# 12-5-3_3_card_concept__panther.net
KiCad netlist of a schematic drawn in EasyEDA Pro
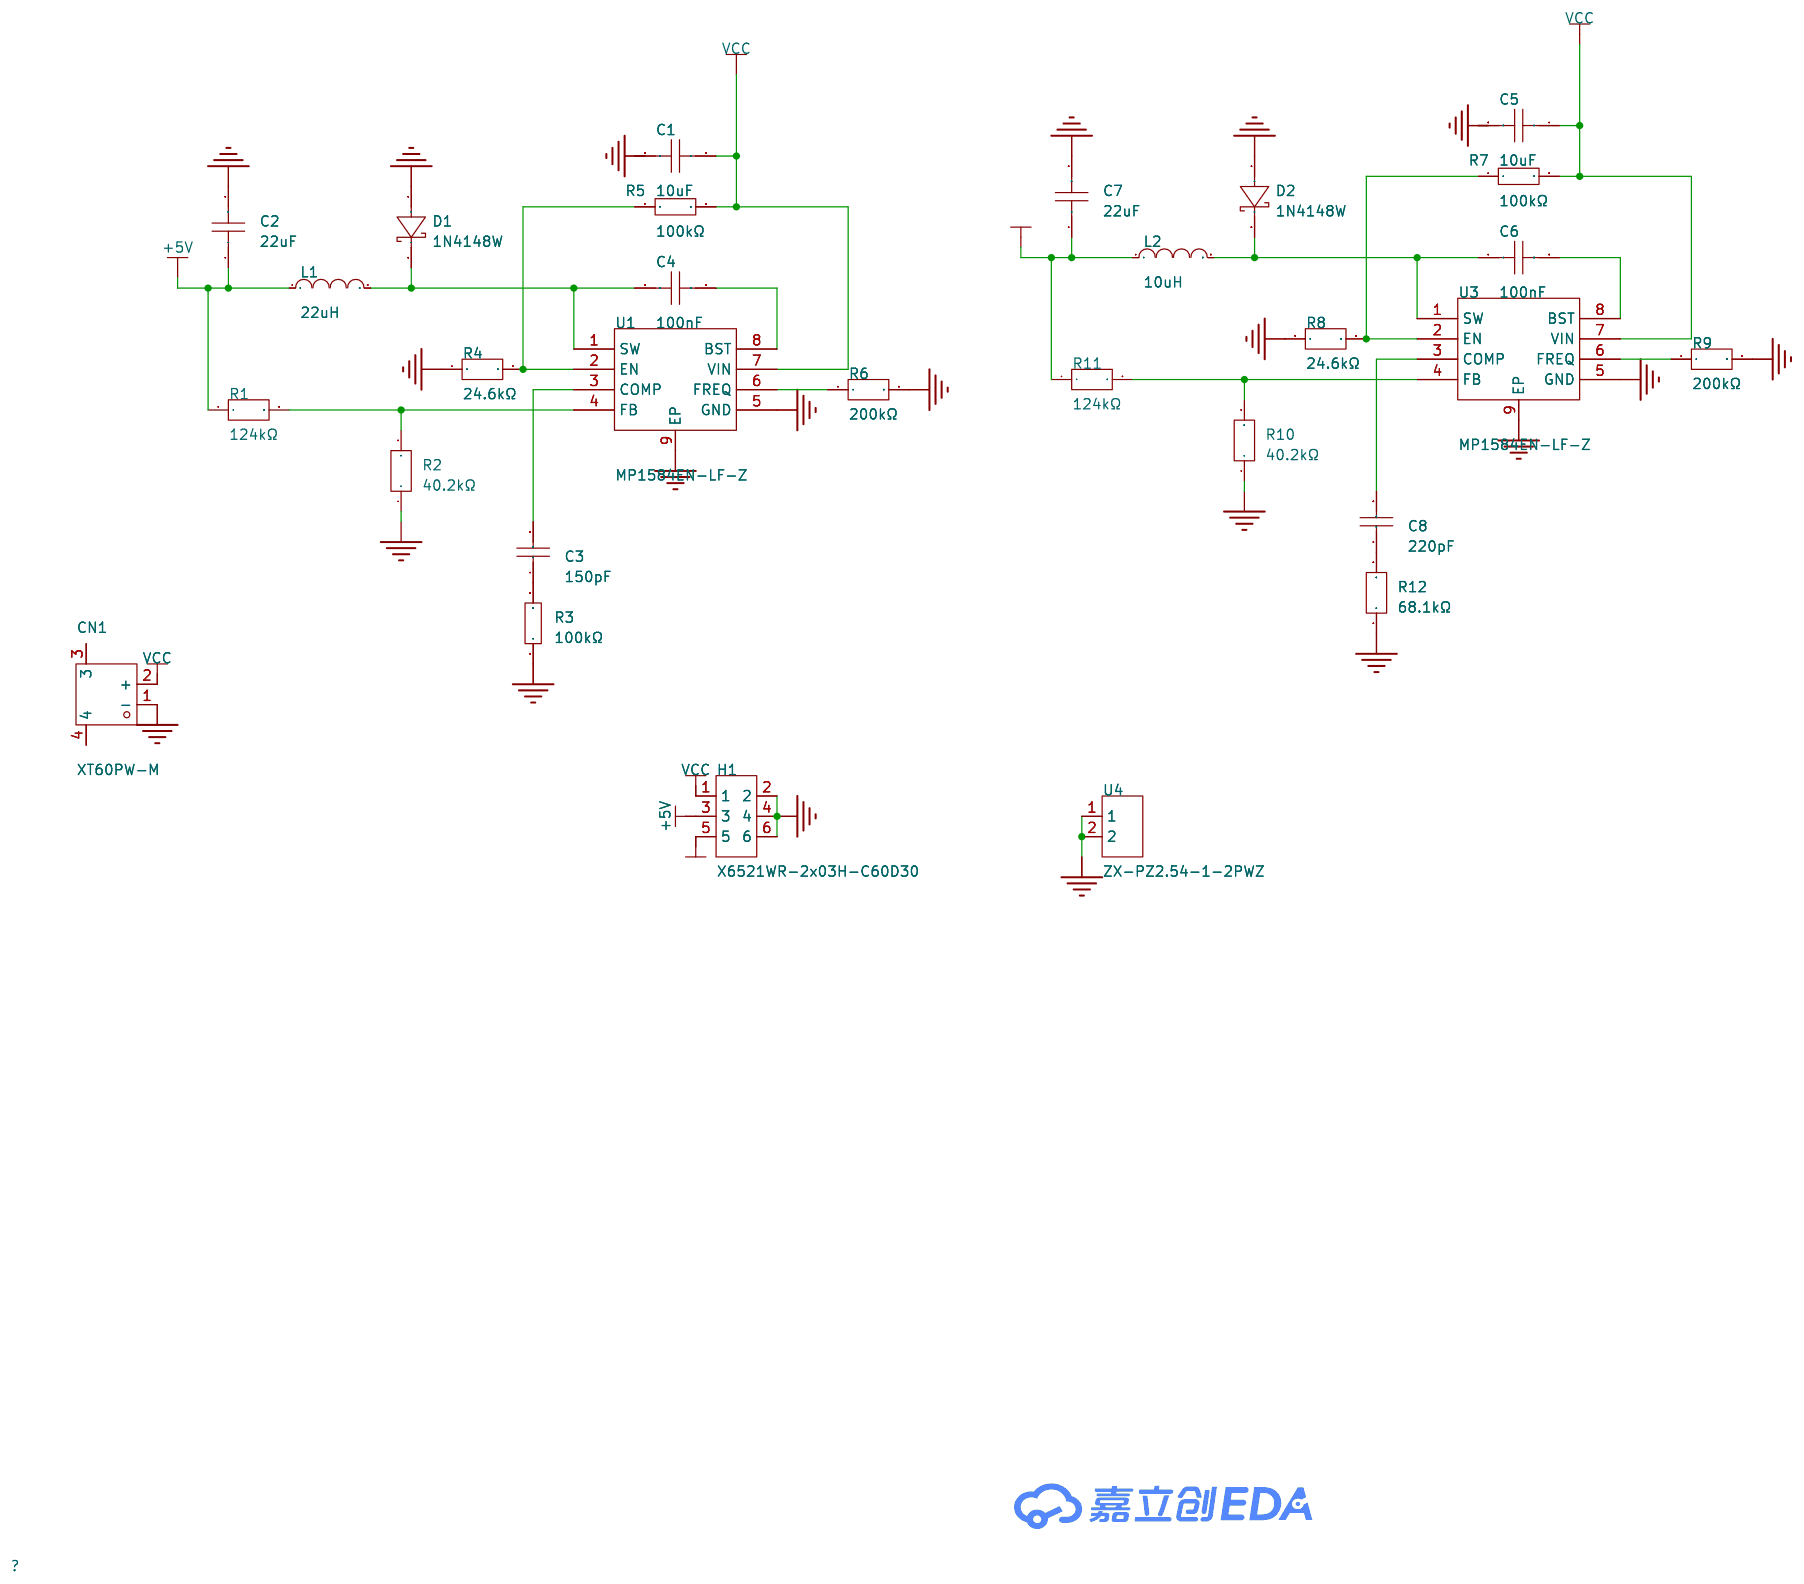
[diagram p0: schematic sheet]

(export (version "E")
  (design (tool "Eeschema 10.0.6"))
  (components
    (comp (ref "C1")
      (value "10uF")
      (footprint "easyedapro:C1206")
      (description "容值:10uF;精度:±10%;额定电压:50V;温度系数:X5R;")
      (fields
        (field (name "Manufacturer Part") "HGC1206R5106K500NSPJ")
        (field (name "Manufacturer") "Chinocera(华瓷)")
      )
      (libsource (lib "easyedapro") (part "HGC1206R5106K500NSPJ"))
    )
    (comp (ref "C2")
      (value "22uF")
      (footprint "easyedapro:C0805")
      (description "容值:22uF;精度:±20%;额定电压:35V;材质(温度系数):X5R;")
      (fields
        (field (name "Manufacturer Part") "CGA0805X5R226M350MT")
        (field (name "Manufacturer") "HRE(芯声)")
      )
      (libsource (lib "easyedapro") (part "CGA0805X5R226M350MT"))
    )
    (comp (ref "C3")
      (value "150pF")
      (footprint "easyedapro:C0603")
      (description "容值:150pF;精度:±10%;额定电压:50V;温度系数:X7R;")
      (fields (field (name "Manufacturer Part") "0603B151K500NT") (field (name "Manufacturer") "FH(风华)"))
      (libsource (lib "easyedapro") (part "0603B151K500NT"))
    )
    (comp (ref "C4")
      (value "100nF")
      (footprint "easyedapro:C0603")
      (description "容值:100nF;精度:±10%;额定电压:50V;材质(温度系数):X7R;")
      (fields
        (field (name "Manufacturer Part") "CGA0603X7R104K500JT")
        (field (name "Manufacturer") "HRE(芯声)")
      )
      (libsource (lib "easyedapro") (part "CGA0603X7R104K500JT"))
    )
    (comp (ref "C5")
      (value "10uF")
      (footprint "easyedapro:C1206")
      (description "容值:10uF;精度:±10%;额定电压:50V;温度系数:X5R;")
      (fields
        (field (name "Manufacturer Part") "HGC1206R5106K500NSPJ")
        (field (name "Manufacturer") "Chinocera(华瓷)")
      )
      (libsource (lib "easyedapro") (part "HGC1206R5106K500NSPJ"))
    )
    (comp (ref "C6")
      (value "100nF")
      (footprint "easyedapro:C0603")
      (description "容值:100nF;精度:±10%;额定电压:50V;材质(温度系数):X7R;")
      (fields
        (field (name "Manufacturer Part") "CGA0603X7R104K500JT")
        (field (name "Manufacturer") "HRE(芯声)")
      )
      (libsource (lib "easyedapro") (part "CGA0603X7R104K500JT"))
    )
    (comp (ref "C7")
      (value "22uF")
      (footprint "easyedapro:C0805")
      (description "容值:22uF;精度:±20%;额定电压:35V;材质(温度系数):X5R;")
      (fields
        (field (name "Manufacturer Part") "CGA0805X5R226M350MT")
        (field (name "Manufacturer") "HRE(芯声)")
      )
      (libsource (lib "easyedapro") (part "CGA0805X5R226M350MT"))
    )
    (comp (ref "C8")
      (value "220pF")
      (footprint "easyedapro:C0603")
      (description "容值:220pF;精度:±10%;额定电压:50V;材质(温度系数):X7R;")
      (fields
        (field (name "Manufacturer Part") "CL10B221KB8NNNC")
        (field (name "Manufacturer") "SAMSUNG(三星)")
      )
      (libsource (lib "easyedapro") (part "CL10B221KB8NNNC"))
    )
    (comp (ref "CN1")
      (value "XT60PW-M")
      (footprint "easyedapro:CONN-TH_XT60PW-M")
      (description "类别:-;类型1:-;")
      (fields (field (name "Manufacturer") "AMASS(艾迈斯)"))
      (libsource (lib "easyedapro") (part "XT60PW-M"))
    )
    (comp (ref "D1")
      (value "1N4148W")
      (footprint "easyedapro:SOD-123_L2.7-W1.6-LS3.7-FD")
      (description "二极管配置:独立式;正向压降(Vf):1.25V@150mA;直流反向耐压(Vr):100V;整流电流:150mA;反向恢复时间(trr):4ns;")
      (fields (field (name "Manufacturer") "宏迦橙"))
      (libsource (lib "easyedapro") (part "1N4148W_C7420318"))
    )
    (comp (ref "D2")
      (value "1N4148W")
      (footprint "easyedapro:SOD-123_L2.7-W1.6-LS3.7-FD")
      (description "二极管配置:独立式;正向压降(Vf):1.25V@150mA;直流反向耐压(Vr):100V;整流电流:150mA;反向恢复时间(trr):4ns;")
      (fields (field (name "Manufacturer") "宏迦橙"))
      (libsource (lib "easyedapro") (part "1N4148W_C7420318"))
    )
    (comp (ref "H1")
      (value "X6521WR-2x03H-C60D30")
      (footprint "easyedapro:HDR-TH_6P-P2.54-H-M-R2-C3-S2.54-W12.3-N")
      (fields (field (name "Manufacturer") "XKB Connection(中国星坤)"))
      (libsource (lib "easyedapro") (part "X6521WR-2×03H-C30D60"))
    )
    (comp (ref "L1")
      (value "22uH")
      (footprint "easyedapro:IND-SMD_L7.0-W6.6_FXL0630")
      (description "电感值:22uH;精度:±20%;额定电流:2.5A;饱和电流(Isat):3A;类型:一体成型电感;")
      (fields (field (name "Manufacturer Part") "FXL0630-220-M") (field (name "Manufacturer") "cjiang(长江微电)"))
      (libsource (lib "easyedapro") (part "FXL0630-220-M"))
    )
    (comp (ref "L2")
      (value "10uH")
      (footprint "easyedapro:IND-SMD_L7.3-W6.8")
      (description "电感值:10uH;精度:±20%;额定电流:4.5A;饱和电流(Isat):5.5A;类型:一体成型电感;")
      (fields (field (name "Manufacturer Part") "FXL0630-100-M") (field (name "Manufacturer") "cjiang(长江微电)"))
      (libsource (lib "easyedapro") (part "FXL0630-100-M"))
    )
    (comp (ref "R1")
      (value "124kΩ")
      (footprint "easyedapro:R0603")
      (description "电阻类型:厚膜电阻;阻值:124kΩ;精度:±1%;功率:100mW;最大工作电压:75V;温度系数:±100ppm/°C;")
      (fields (field (name "Manufacturer Part") "FRC0603F1243TS") (field (name "Manufacturer") "FOJAN(富捷)"))
      (libsource (lib "easyedapro") (part "FRC0603F1243TS"))
    )
    (comp (ref "R2")
      (value "40.2kΩ")
      (footprint "easyedapro:R0603")
      (description "电阻类型:厚膜电阻;阻值:40.2kΩ;精度:±1%;功率:100mW;最大工作电压:75V;温度系数:±100ppm/°C;")
      (fields (field (name "Manufacturer Part") "FRC0603F4022TS") (field (name "Manufacturer") "FOJAN(富捷)"))
      (libsource (lib "easyedapro") (part "FRC0603F4022TS"))
    )
    (comp (ref "R3")
      (value "100kΩ")
      (footprint "easyedapro:R0603")
      (description "电阻类型:厚膜电阻;阻值:100kΩ;精度:±1%;功率:100mW;最大工作电压:75V;温度系数:±100ppm/°C;")
      (fields
        (field (name "Manufacturer Part") "0603WAF1003T5E")
        (field (name "Manufacturer") "UNI-ROYAL(厚声)")
      )
      (libsource (lib "easyedapro") (part "0603WAF1003T5E"))
    )
    (comp (ref "R4")
      (value "24.6kΩ")
      (footprint "easyedapro:R0603")
      (description "电阻类型:薄膜电阻;阻值:24.6kΩ;精度:±0.1%;功率:100mW;温度系数:±25ppm/°C;")
      (fields (field (name "Manufacturer Part") "RT0603BRD0724K6L") (field (name "Manufacturer") "YAGEO(国巨)"))
      (libsource (lib "easyedapro") (part "RT0603BRD0724K6L"))
    )
    (comp (ref "R5")
      (value "100kΩ")
      (footprint "easyedapro:R0603")
      (description "电阻类型:厚膜电阻;阻值:100kΩ;精度:±1%;功率:100mW;最大工作电压:75V;温度系数:±100ppm/°C;")
      (fields
        (field (name "Manufacturer Part") "0603WAF1003T5E")
        (field (name "Manufacturer") "UNI-ROYAL(厚声)")
      )
      (libsource (lib "easyedapro") (part "0603WAF1003T5E"))
    )
    (comp (ref "R6")
      (value "200kΩ")
      (footprint "easyedapro:R0603")
      (description "电阻类型:厚膜电阻;阻值:200kΩ;精度:±1%;功率:100mW;工作电压:75V;温度系数:±100ppm/°C;")
      (fields (field (name "Manufacturer Part") "FRC0603F2003TS") (field (name "Manufacturer") "FOJAN(富捷)"))
      (libsource (lib "easyedapro") (part "FRC0603F2003TS"))
    )
    (comp (ref "R7")
      (value "100kΩ")
      (footprint "easyedapro:R0603")
      (description "电阻类型:厚膜电阻;阻值:100kΩ;精度:±1%;功率:100mW;最大工作电压:75V;温度系数:±100ppm/°C;")
      (fields
        (field (name "Manufacturer Part") "0603WAF1003T5E")
        (field (name "Manufacturer") "UNI-ROYAL(厚声)")
      )
      (libsource (lib "easyedapro") (part "0603WAF1003T5E"))
    )
    (comp (ref "R8")
      (value "24.6kΩ")
      (footprint "easyedapro:R0603")
      (description "电阻类型:薄膜电阻;阻值:24.6kΩ;精度:±0.1%;功率:100mW;温度系数:±25ppm/°C;")
      (fields (field (name "Manufacturer Part") "RT0603BRD0724K6L") (field (name "Manufacturer") "YAGEO(国巨)"))
      (libsource (lib "easyedapro") (part "RT0603BRD0724K6L"))
    )
    (comp (ref "R9")
      (value "200kΩ")
      (footprint "easyedapro:R0603")
      (description "电阻类型:厚膜电阻;阻值:200kΩ;精度:±1%;功率:100mW;工作电压:75V;温度系数:±100ppm/°C;")
      (fields (field (name "Manufacturer Part") "FRC0603F2003TS") (field (name "Manufacturer") "FOJAN(富捷)"))
      (libsource (lib "easyedapro") (part "FRC0603F2003TS"))
    )
    (comp (ref "R10")
      (value "40.2kΩ")
      (footprint "easyedapro:R0603")
      (description "电阻类型:厚膜电阻;阻值:40.2kΩ;精度:±1%;功率:100mW;最大工作电压:75V;温度系数:±100ppm/°C;")
      (fields (field (name "Manufacturer Part") "FRC0603F4022TS") (field (name "Manufacturer") "FOJAN(富捷)"))
      (libsource (lib "easyedapro") (part "FRC0603F4022TS"))
    )
    (comp (ref "R11")
      (value "124kΩ")
      (footprint "easyedapro:R0603")
      (description "电阻类型:厚膜电阻;阻值:124kΩ;精度:±1%;功率:100mW;最大工作电压:75V;温度系数:±100ppm/°C;")
      (fields (field (name "Manufacturer Part") "FRC0603F1243TS") (field (name "Manufacturer") "FOJAN(富捷)"))
      (libsource (lib "easyedapro") (part "FRC0603F1243TS"))
    )
    (comp (ref "R12")
      (value "68.1kΩ")
      (footprint "easyedapro:R0603")
      (description "电阻类型:厚膜电阻;阻值:68.1kΩ;精度:±1%;功率:100mW;最大工作电压:75V;温度系数:±100ppm/°C;")
      (fields (field (name "Manufacturer Part") "FRC0603F6812TS") (field (name "Manufacturer") "FOJAN(富捷)"))
      (libsource (lib "easyedapro") (part "FRC0603F6812TS"))
    )
    (comp (ref "U1")
      (value "MP1584EN-LF-Z")
      (footprint "easyedapro:SOIC-8_L5.0-W4.0-P1.27-LS6.0-BL-EP2.0")
      (description "功能类型:降压型;输出类型:固定;工作电压:4.5V~28V;输出电压:800mV~25V;输出电流:3A;")
      (fields (field (name "Manufacturer") "MPS(芯源)"))
      (libsource (lib "easyedapro") (part "MP1584EN-LF-Z"))
    )
    (comp (ref "U3")
      (value "MP1584EN-LF-Z")
      (footprint "easyedapro:SOIC-8_L5.0-W4.0-P1.27-LS6.0-BL-EP2.0")
      (description "功能类型:降压型;输出类型:固定;工作电压:4.5V~28V;输出电压:800mV~25V;输出电流:3A;")
      (fields (field (name "Manufacturer") "MPS(芯源)"))
      (libsource (lib "easyedapro") (part "MP1584EN-LF-Z"))
    )
    (comp (ref "U4")
      (value "ZX-PZ2.54-1-2PWZ")
      (footprint "easyedapro:HDR-TH_2P-P2.54-H-M-W10.4")
      (fields (field (name "Manufacturer") "Megastar(兆星)"))
      (libsource (lib "easyedapro") (part "ZX-PZ2.54-1-2PWZ"))
    )
  )
  (nets
    (net (code "1") (name "+3.3V") (class "Default")
      (node (ref "C7") (pin "1") (pinfunction "1_1") (pintype "unspecified"))
      (node (ref "H1") (pin "5") (pinfunction "5_5") (pintype "unspecified"))
      (node (ref "L2") (pin "1") (pinfunction "1_1") (pintype "unspecified"))
      (node (ref "R11") (pin "1") (pinfunction "1_1") (pintype "unspecified"))
    )
    (net (code "2") (name "+5V") (class "Default")
      (node (ref "C2") (pin "1") (pinfunction "1_1") (pintype "unspecified"))
      (node (ref "H1") (pin "3") (pinfunction "3_3") (pintype "unspecified"))
      (node (ref "L1") (pin "1") (pinfunction "1_1") (pintype "unspecified"))
      (node (ref "R1") (pin "1") (pinfunction "1_1") (pintype "unspecified"))
    )
    (net (code "3") (name "GND") (class "Default")
      (node (ref "C1") (pin "2") (pinfunction "2_2") (pintype "unspecified"))
      (node (ref "C2") (pin "2") (pinfunction "2_2") (pintype "unspecified"))
      (node (ref "C5") (pin "2") (pinfunction "2_2") (pintype "unspecified"))
      (node (ref "C7") (pin "2") (pinfunction "2_2") (pintype "unspecified"))
      (node (ref "CN1") (pin "1") (pinfunction "-_1") (pintype "unspecified"))
      (node (ref "D1") (pin "1") (pinfunction "A_1") (pintype "unspecified"))
      (node (ref "D2") (pin "1") (pinfunction "A_1") (pintype "unspecified"))
      (node (ref "H1") (pin "2") (pinfunction "2_2") (pintype "unspecified"))
      (node (ref "H1") (pin "4") (pinfunction "4_4") (pintype "unspecified"))
      (node (ref "H1") (pin "6") (pinfunction "6_6") (pintype "unspecified"))
      (node (ref "R10") (pin "1") (pinfunction "1_1") (pintype "unspecified"))
      (node (ref "R12") (pin "1") (pinfunction "1_1") (pintype "unspecified"))
      (node (ref "R2") (pin "1") (pinfunction "1_1") (pintype "unspecified"))
      (node (ref "R3") (pin "1") (pinfunction "1_1") (pintype "input"))
      (node (ref "R4") (pin "1") (pinfunction "1_1") (pintype "unspecified"))
      (node (ref "R6") (pin "2") (pinfunction "2_2") (pintype "unspecified"))
      (node (ref "R8") (pin "1") (pinfunction "1_1") (pintype "unspecified"))
      (node (ref "R9") (pin "2") (pinfunction "2_2") (pintype "unspecified"))
      (node (ref "U1") (pin "5") (pinfunction "GND_5") (pintype "unspecified"))
      (node (ref "U1") (pin "9") (pinfunction "EP_9") (pintype "unspecified"))
      (node (ref "U3") (pin "5") (pinfunction "GND_5") (pintype "unspecified"))
      (node (ref "U3") (pin "9") (pinfunction "EP_9") (pintype "unspecified"))
      (node (ref "U4") (pin "1") (pinfunction "1_1") (pintype "unspecified"))
      (node (ref "U4") (pin "2") (pinfunction "2_2") (pintype "unspecified"))
    )
    (net (code "4") (name "Net-(C3-Pad1)") (class "Default")
      (node (ref "C3") (pin "1") (pinfunction "1_1") (pintype "input"))
      (node (ref "R3") (pin "2") (pinfunction "2_2") (pintype "input"))
    )
    (net (code "5") (name "Net-(C8-Pad1)") (class "Default")
      (node (ref "C8") (pin "1") (pinfunction "1_1") (pintype "input"))
      (node (ref "R12") (pin "2") (pinfunction "2_2") (pintype "unspecified"))
    )
    (net (code "6") (name "Net-(D1-K)") (class "Default")
      (node (ref "C4") (pin "1") (pinfunction "1_1") (pintype "unspecified"))
      (node (ref "D1") (pin "2") (pinfunction "K_2") (pintype "unspecified"))
      (node (ref "L1") (pin "2") (pinfunction "2_2") (pintype "unspecified"))
      (node (ref "U1") (pin "1") (pinfunction "SW_1") (pintype "unspecified"))
    )
    (net (code "7") (name "Net-(D2-K)") (class "Default")
      (node (ref "C6") (pin "1") (pinfunction "1_1") (pintype "unspecified"))
      (node (ref "D2") (pin "2") (pinfunction "K_2") (pintype "unspecified"))
      (node (ref "L2") (pin "2") (pinfunction "2_2") (pintype "unspecified"))
      (node (ref "U3") (pin "1") (pinfunction "SW_1") (pintype "unspecified"))
    )
    (net (code "8") (name "Net-(U1-BST)") (class "Default")
      (node (ref "C4") (pin "2") (pinfunction "2_2") (pintype "unspecified"))
      (node (ref "U1") (pin "8") (pinfunction "BST_8") (pintype "unspecified"))
    )
    (net (code "9") (name "Net-(U1-COMP)") (class "Default")
      (node (ref "C3") (pin "2") (pinfunction "2_2") (pintype "input"))
      (node (ref "U1") (pin "3") (pinfunction "COMP_3") (pintype "unspecified"))
    )
    (net (code "10") (name "Net-(U1-EN)") (class "Default")
      (node (ref "R4") (pin "2") (pinfunction "2_2") (pintype "unspecified"))
      (node (ref "R5") (pin "1") (pinfunction "1_1") (pintype "input"))
      (node (ref "U1") (pin "2") (pinfunction "EN_2") (pintype "unspecified"))
    )
    (net (code "11") (name "Net-(U1-FB)") (class "Default")
      (node (ref "R1") (pin "2") (pinfunction "2_2") (pintype "unspecified"))
      (node (ref "R2") (pin "2") (pinfunction "2_2") (pintype "unspecified"))
      (node (ref "U1") (pin "4") (pinfunction "FB_4") (pintype "unspecified"))
    )
    (net (code "12") (name "Net-(U1-FREQ)") (class "Default")
      (node (ref "R6") (pin "1") (pinfunction "1_1") (pintype "unspecified"))
      (node (ref "U1") (pin "6") (pinfunction "FREQ_6") (pintype "unspecified"))
    )
    (net (code "13") (name "Net-(U3-BST)") (class "Default")
      (node (ref "C6") (pin "2") (pinfunction "2_2") (pintype "unspecified"))
      (node (ref "U3") (pin "8") (pinfunction "BST_8") (pintype "unspecified"))
    )
    (net (code "14") (name "Net-(U3-COMP)") (class "Default")
      (node (ref "C8") (pin "2") (pinfunction "2_2") (pintype "input"))
      (node (ref "U3") (pin "3") (pinfunction "COMP_3") (pintype "unspecified"))
    )
    (net (code "15") (name "Net-(U3-EN)") (class "Default")
      (node (ref "R7") (pin "1") (pinfunction "1_1") (pintype "input"))
      (node (ref "R8") (pin "2") (pinfunction "2_2") (pintype "unspecified"))
      (node (ref "U3") (pin "2") (pinfunction "EN_2") (pintype "unspecified"))
    )
    (net (code "16") (name "Net-(U3-FB)") (class "Default")
      (node (ref "R10") (pin "2") (pinfunction "2_2") (pintype "unspecified"))
      (node (ref "R11") (pin "2") (pinfunction "2_2") (pintype "unspecified"))
      (node (ref "U3") (pin "4") (pinfunction "FB_4") (pintype "unspecified"))
    )
    (net (code "17") (name "Net-(U3-FREQ)") (class "Default")
      (node (ref "R9") (pin "1") (pinfunction "1_1") (pintype "unspecified"))
      (node (ref "U3") (pin "6") (pinfunction "FREQ_6") (pintype "unspecified"))
    )
    (net (code "18") (name "VCC") (class "Default")
      (node (ref "C1") (pin "1") (pinfunction "1_1") (pintype "unspecified"))
      (node (ref "C5") (pin "1") (pinfunction "1_1") (pintype "unspecified"))
      (node (ref "CN1") (pin "2") (pinfunction "+_2") (pintype "unspecified"))
      (node (ref "H1") (pin "1") (pinfunction "1_1") (pintype "unspecified"))
      (node (ref "R5") (pin "2") (pinfunction "2_2") (pintype "input"))
      (node (ref "R7") (pin "2") (pinfunction "2_2") (pintype "input"))
      (node (ref "U1") (pin "7") (pinfunction "VIN_7") (pintype "unspecified"))
      (node (ref "U3") (pin "7") (pinfunction "VIN_7") (pintype "unspecified"))
    )
    (net (code "19") (name "unconnected-(CN1-Pad3)") (class "Default")
      (node (ref "CN1") (pin "3") (pinfunction "3_3") (pintype "unspecified"))
    )
    (net (code "20") (name "unconnected-(CN1-Pad4)") (class "Default")
      (node (ref "CN1") (pin "4") (pinfunction "4_4") (pintype "unspecified"))
    )
  )
)
